# E-20_EXP_MicroSD_ADC.net
KiCad netlist of a schematic drawn in Altium Designer
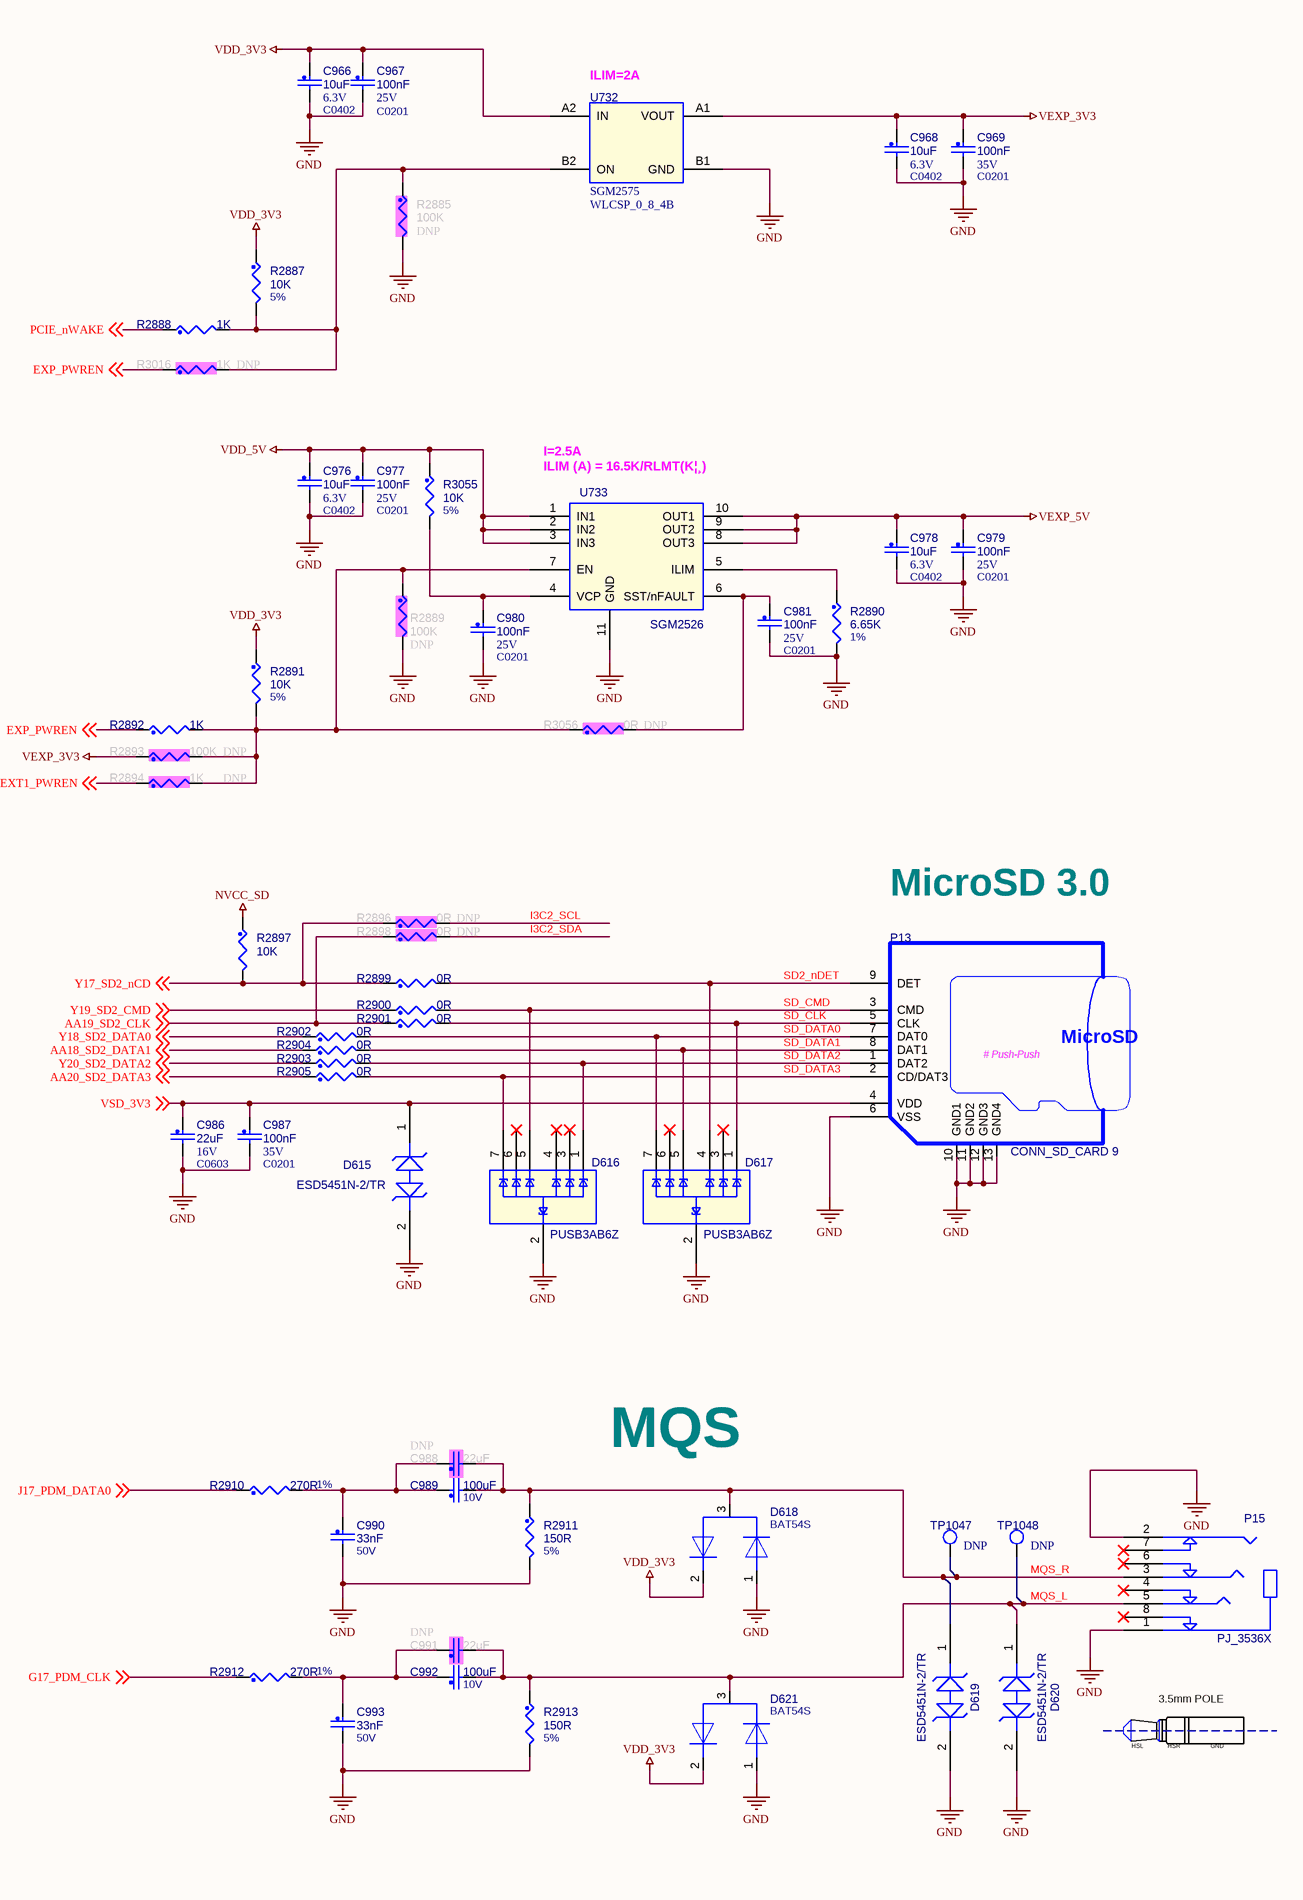
[diagram p0: E-20 EXP_MicroSD_ADC.SchDoc, left]
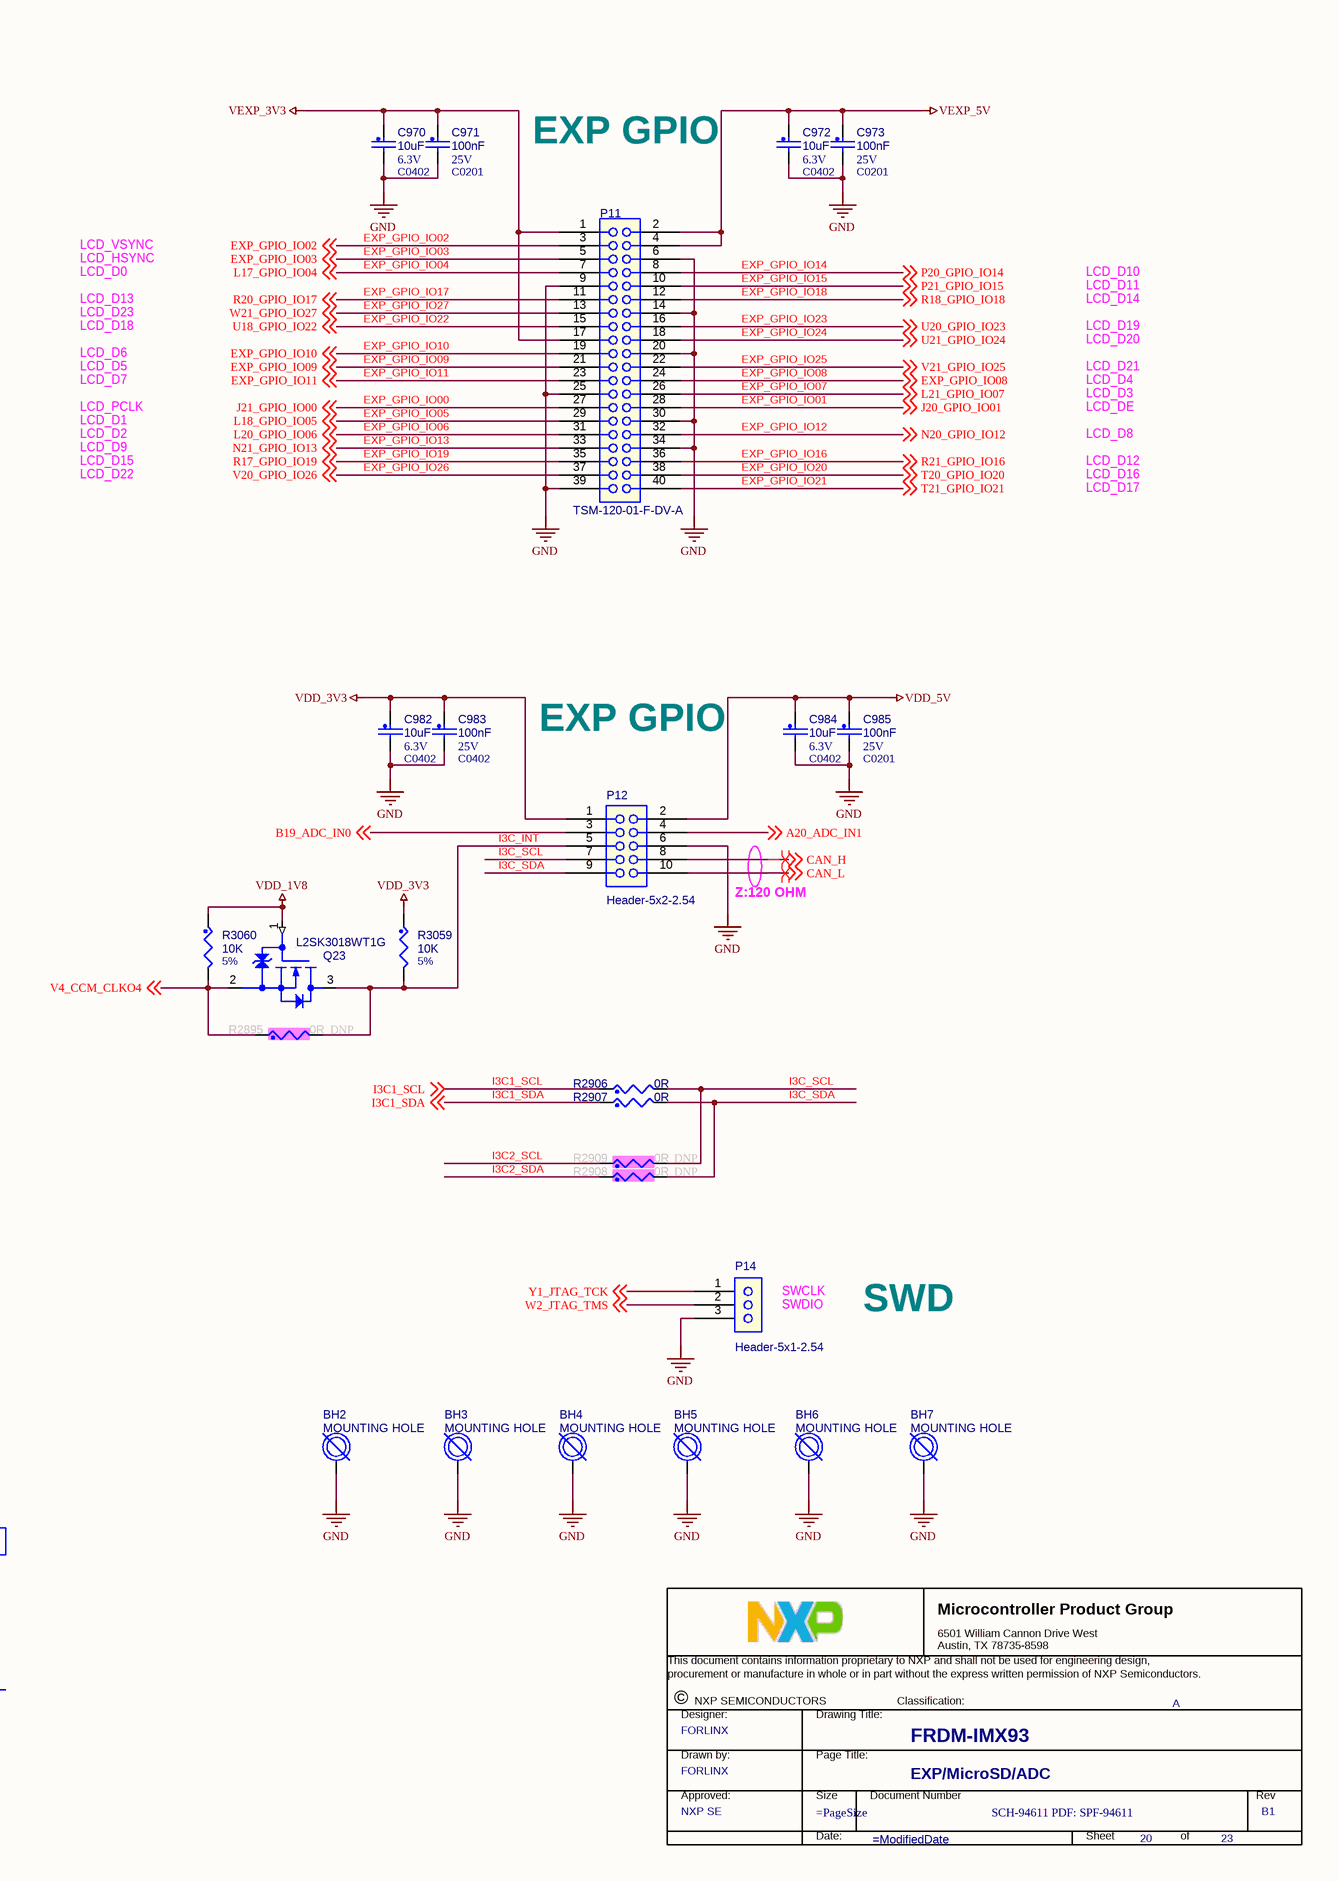
[diagram p1: E-20 EXP_MicroSD_ADC.SchDoc, right]

(export (version "E")
  (design (tool "Eeschema 10.0.6"))
  (components
    (comp (ref "BH2")
      (value "MOUNTING HOLE")
      (footprint "HOLE2_7_6")
      (description "no part to order")
      (libsource (lib "*") (part "MOUNT_HOLE"))
    )
    (comp (ref "BH3")
      (value "MOUNTING HOLE")
      (footprint "HOLE2_7_6")
      (description "no part to order")
      (libsource (lib "*") (part "MOUNT_HOLE"))
    )
    (comp (ref "BH4")
      (value "MOUNTING HOLE")
      (footprint "HOLE2_7_6")
      (description "no part to order")
      (libsource (lib "*") (part "MOUNT_HOLE"))
    )
    (comp (ref "BH5")
      (value "MOUNTING HOLE")
      (footprint "HOLE2_7_6")
      (description "no part to order")
      (libsource (lib "*") (part "MOUNT_HOLE"))
    )
    (comp (ref "BH6")
      (value "MOUNTING HOLE")
      (footprint "HOLE2_7_6")
      (description "no part to order")
      (libsource (lib "*") (part "MOUNT_HOLE"))
    )
    (comp (ref "BH7")
      (value "MOUNTING HOLE")
      (footprint "HOLE2_7_6")
      (description "no part to order")
      (libsource (lib "*") (part "MOUNT_HOLE"))
    )
    (comp (ref "C966")
      (value "10uF")
      (footprint "C0402")
      (description "0402,10uF,6.3V,+/-20%,X5R")
      (fields
        (field (name "TOLERANCE") "20%")
        (field (name "VOLTAGE") "6.3V")
        (field (name "PCB FOOTPRINT") "C0402")
      )
      (libsource (lib "*") (part "CAP_NP"))
    )
    (comp (ref "C967")
      (value "100nF")
      (footprint "C0201")
      (description "0201,100nF,25V,+/-10%,X5R")
      (fields
        (field (name "TOLERANCE") "10%")
        (field (name "VOLTAGE") "25V")
        (field (name "PCB FOOTPRINT") "C0201")
      )
      (libsource (lib "*") (part "CAP_NP"))
    )
    (comp (ref "C968")
      (value "10uF")
      (footprint "C0402")
      (description "0402,10uF,6.3V,+/-20%,X5R")
      (fields
        (field (name "VOLTAGE") "6.3V")
        (field (name "TOLERANCE") "20%")
        (field (name "PCB FOOTPRINT") "C0402")
      )
      (libsource (lib "*") (part "CAP_NP"))
    )
    (comp (ref "C969")
      (value "100nF")
      (footprint "C0201")
      (description "0201,100nF,25V,+/-10%,X5R")
      (fields
        (field (name "VOLTAGE") "35V")
        (field (name "TOLERANCE") "10%")
        (field (name "PCB FOOTPRINT") "C0201")
      )
      (libsource (lib "*") (part "CAP_NP"))
    )
    (comp (ref "C970")
      (value "10uF")
      (footprint "C0402")
      (description "0402,10uF,6.3V,+/-20%,X5R")
      (fields
        (field (name "VOLTAGE") "6.3V")
        (field (name "TOLERANCE") "20%")
        (field (name "PCB FOOTPRINT") "C0402")
      )
      (libsource (lib "*") (part "CAP_NP"))
    )
    (comp (ref "C971")
      (value "100nF")
      (footprint "C0201")
      (description "0201,100nF,25V,+/-10%,X5R")
      (fields
        (field (name "TOLERANCE") "10%")
        (field (name "VOLTAGE") "25V")
        (field (name "PCB FOOTPRINT") "C0201")
      )
      (libsource (lib "*") (part "CAP_NP"))
    )
    (comp (ref "C972")
      (value "10uF")
      (footprint "C0402")
      (description "0402,10uF,6.3V,+/-20%,X5R")
      (fields
        (field (name "VOLTAGE") "6.3V")
        (field (name "TOLERANCE") "20%")
        (field (name "PCB FOOTPRINT") "C0402")
      )
      (libsource (lib "*") (part "CAP_NP"))
    )
    (comp (ref "C973")
      (value "100nF")
      (footprint "C0201")
      (description "0201,100nF,25V,+/-10%,X5R")
      (fields
        (field (name "VOLTAGE") "25V")
        (field (name "TOLERANCE") "10%")
        (field (name "PCB FOOTPRINT") "C0201")
      )
      (libsource (lib "*") (part "CAP_NP"))
    )
    (comp (ref "C976")
      (value "10uF")
      (footprint "C0402")
      (description "0402,10uF,6.3V,+/-20%,X5R")
      (fields
        (field (name "VOLTAGE") "6.3V")
        (field (name "TOLERANCE") "20%")
        (field (name "PCB FOOTPRINT") "C0402")
      )
      (libsource (lib "*") (part "CAP_NP"))
    )
    (comp (ref "C977")
      (value "100nF")
      (footprint "C0201")
      (description "0201,100nF,25V,+/-10%,X5R")
      (fields
        (field (name "VOLTAGE") "25V")
        (field (name "TOLERANCE") "10%")
        (field (name "PCB FOOTPRINT") "C0201")
      )
      (libsource (lib "*") (part "CAP_NP"))
    )
    (comp (ref "C978")
      (value "10uF")
      (footprint "C0402")
      (description "0402,10uF,6.3V,+/-20%,X5R")
      (fields
        (field (name "TOLERANCE") "20%")
        (field (name "VOLTAGE") "6.3V")
        (field (name "PCB FOOTPRINT") "C0402")
      )
      (libsource (lib "*") (part "CAP_NP"))
    )
    (comp (ref "C979")
      (value "100nF")
      (footprint "C0201")
      (description "0201,100nF,25V,+/-10%,X5R")
      (fields
        (field (name "VOLTAGE") "25V")
        (field (name "TOLERANCE") "10%")
        (field (name "PCB FOOTPRINT") "C0201")
      )
      (libsource (lib "*") (part "CAP_NP"))
    )
    (comp (ref "C980")
      (value "100nF")
      (footprint "C0201")
      (description "0201,100nF,25V,+/-10%,X5R")
      (fields
        (field (name "TOLERANCE") "10%")
        (field (name "VOLTAGE") "25V")
        (field (name "PCB FOOTPRINT") "C0201")
      )
      (libsource (lib "*") (part "CAP_NP"))
    )
    (comp (ref "C981")
      (value "100nF")
      (footprint "C0201")
      (description "0201,100nF,25V,+/-10%,X5R")
      (fields
        (field (name "VOLTAGE") "25V")
        (field (name "TOLERANCE") "10%")
        (field (name "PCB FOOTPRINT") "C0201")
      )
      (libsource (lib "*") (part "CAP_NP"))
    )
    (comp (ref "C982")
      (value "10uF")
      (footprint "C0402")
      (description "0402,10uF,6.3V,+/-20%,X5R")
      (fields
        (field (name "TOLERANCE") "20%")
        (field (name "VOLTAGE") "6.3V")
        (field (name "PCB FOOTPRINT") "C0402")
      )
      (libsource (lib "*") (part "CAP_NP"))
    )
    (comp (ref "C983")
      (value "100nF")
      (footprint "C0402")
      (description "0402,100nF,50V,+/-10%,X5R")
      (fields
        (field (name "TOLERANCE") "10%")
        (field (name "VOLTAGE") "25V")
        (field (name "PCB FOOTPRINT") "C0402")
      )
      (libsource (lib "*") (part "CAP_NP"))
    )
    (comp (ref "C984")
      (value "10uF")
      (footprint "C0402")
      (description "0402,10uF,6.3V,+/-20%,X5R")
      (fields
        (field (name "VOLTAGE") "6.3V")
        (field (name "TOLERANCE") "20%")
        (field (name "PCB FOOTPRINT") "C0402")
      )
      (libsource (lib "*") (part "CAP_NP"))
    )
    (comp (ref "C985")
      (value "100nF")
      (footprint "C0201")
      (description "0201,100nF,25V,+/-10%,X5R")
      (fields
        (field (name "VOLTAGE") "25V")
        (field (name "TOLERANCE") "10%")
        (field (name "PCB FOOTPRINT") "C0201")
      )
      (libsource (lib "*") (part "CAP_NP"))
    )
    (comp (ref "C986")
      (value "22uF")
      (footprint "C0603")
      (description "0603,22uF,6.3V,+/-20%,X5R")
      (fields
        (field (name "VOLTAGE") "16V")
        (field (name "TOLERANCE") "20%")
        (field (name "PCB FOOTPRINT") "C0603")
      )
      (libsource (lib "*") (part "CAP_NP"))
    )
    (comp (ref "C987")
      (value "100nF")
      (footprint "C0201")
      (description "0201,100nF,25V,+/-10%,X5R")
      (fields
        (field (name "TOLERANCE") "10%")
        (field (name "VOLTAGE") "35V")
        (field (name "PCB FOOTPRINT") "C0201")
      )
      (libsource (lib "*") (part "CAP_NP"))
    )
    (comp (ref "C988")
      (value "22uF")
      (footprint "C0805")
      (description "0805,22uF,25V,+/-20%,X5R")
      (fields (field (name "ASSY_OPT") "DNP") (field (name "TOLERANCE") "20%"))
      (libsource (lib "*") (part "CAP_NP"))
    )
    (comp (ref "C989")
      (value "100uF")
      (footprint "C1206")
      (description "1206,100uF,6.3V,+/-20%,X5R")
      (fields (field (name "VOLTAGE") "10V") (field (name "TOLERANCE") "20%"))
      (libsource (lib "*") (part "CAP_NP"))
    )
    (comp (ref "C990")
      (value "33nF")
      (footprint "C0402")
      (description "0402,33nF,50V,+/-10%,X7R")
      (fields (field (name "VOLTAGE") "50V") (field (name "TOLERANCE") "10%"))
      (libsource (lib "*") (part "CAP_NP"))
    )
    (comp (ref "C991")
      (value "22uF")
      (footprint "C0805")
      (description "0805,22uF,25V,+/-20%,X5R")
      (fields (field (name "ASSY_OPT") "DNP") (field (name "TOLERANCE") "20%"))
      (libsource (lib "*") (part "CAP_NP"))
    )
    (comp (ref "C992")
      (value "100uF")
      (footprint "C1206")
      (description "1206,100uF,6.3V,+/-20%,X5R")
      (fields (field (name "VOLTAGE") "10V") (field (name "TOLERANCE") "20%"))
      (libsource (lib "*") (part "CAP_NP"))
    )
    (comp (ref "C993")
      (value "33nF")
      (footprint "C0402")
      (description "0402,33nF,50V,+/-10%,X7R")
      (fields (field (name "TOLERANCE") "10%") (field (name "VOLTAGE") "50V"))
      (libsource (lib "*") (part "CAP_NP"))
    )
    (comp (ref "D615")
      (value "ESD5451N-2/TR")
      (footprint "0402TVS")
      (libsource (lib "*") (part "ESD5451N-2/TR"))
    )
    (comp (ref "D616") (value "PUSB3AB6Z") (footprint "DFN2111_7") (libsource (lib "*") (part "PUSB3AB6Z")))
    (comp (ref "D617") (value "PUSB3AB6Z") (footprint "DFN2111_7") (libsource (lib "*") (part "PUSB3AB6Z")))
    (comp (ref "D618")
      (value "BAT54S")
      (footprint "sot23_a")
      (description "BAT54S,SOT-23-3")
      (libsource (lib "*") (part "BAV99W"))
    )
    (comp (ref "D619")
      (value "ESD5451N-2/TR")
      (footprint "0402TVS")
      (libsource (lib "*") (part "ESD5451N-2/TR"))
    )
    (comp (ref "D620")
      (value "ESD5451N-2/TR")
      (footprint "0402TVS")
      (libsource (lib "*") (part "ESD5451N-2/TR"))
    )
    (comp (ref "D621")
      (value "BAT54S")
      (footprint "sot23_a")
      (description "BAT54S,SOT-23-3")
      (libsource (lib "*") (part "BAV99W"))
    )
    (comp (ref "P11")
      (value "TSM-120-01-F-DV-A")
      (footprint "hdr220_tsm_a_sm")
      (description "Double row, 2 * 20P, 2.54mm, S, gold-plated, green")
      (libsource (lib "*") (part "CONN_HDR_19"))
    )
    (comp (ref "P12")
      (value "Header-5x2-2.54")
      (footprint "Header5x2_25")
      (description "Double row,2*5P,2.54mm,S")
      (libsource (lib "*") (part "Header-5x2-2_0.54"))
    )
    (comp (ref "P13")
      (value "CONN_SD_CARD 9")
      (footprint "con9_sdcard_1p1mm")
      (description "TFP09-2-12B")
      (libsource (lib "*") (part "CONN_MICRO_SDCARD"))
    )
    (comp (ref "P14")
      (value "Header-5x1-2.54")
      (footprint "Header_2_54_3p")
      (description "Single row,3P,2.54mm,S")
      (libsource (lib "*") (part "Header-5x1-2_0.54"))
    )
    (comp (ref "P15")
      (value "PJ_3536X")
      (footprint "PJ3930_8P")
      (description "PJ3930-8P,3.5mm,Level 4")
      (libsource (lib "*") (part "PJ_3536X"))
    )
    (comp (ref "Q23")
      (value "L2SK3018WT1G")
      (footprint "sc70_3")
      (libsource (lib "*") (part "NX3008NBKW_SOT323"))
    )
    (comp (ref "R2885")
      (value "100K")
      (footprint "R0201")
      (description "0201,100K,+/-1%")
      (fields (field (name "ASSY_OPT") "DNP") (field (name "TOLERANCE") "1%"))
      (libsource (lib "*") (part "RES"))
    )
    (comp (ref "R2887")
      (value "10K")
      (footprint "R0201")
      (description "0201,10K,+/-5%")
      (fields (field (name "TOLERANCE") "5%"))
      (libsource (lib "*") (part "RES"))
    )
    (comp (ref "R2888")
      (value "1K")
      (footprint "R0201")
      (description "0201,1K,+/-1%")
      (fields (field (name "VOLTAGE") "1/16W") (field (name "TOLERANCE") "5%"))
      (libsource (lib "*") (part "RES"))
    )
    (comp (ref "R2889")
      (value "100K")
      (footprint "R0201")
      (description "0201,100K,+/-1%")
      (fields (field (name "ASSY_OPT") "DNP") (field (name "TOLERANCE") "1%"))
      (libsource (lib "*") (part "RES"))
    )
    (comp (ref "R2890")
      (value "6.65K")
      (footprint "R0402")
      (description "0402,6.65K,+/-1%")
      (fields (field (name "TOLERANCE") "1%"))
      (libsource (lib "*") (part "RES"))
    )
    (comp (ref "R2891")
      (value "10K")
      (footprint "R0201")
      (description "0201,10K,+/-5%")
      (fields (field (name "TOLERANCE") "5%"))
      (libsource (lib "*") (part "RES"))
    )
    (comp (ref "R2892")
      (value "1K")
      (footprint "R0201")
      (description "0201,1K,+/-1%")
      (fields (field (name "VOLTAGE") "1/16W") (field (name "TOLERANCE") "5%"))
      (libsource (lib "*") (part "RES"))
    )
    (comp (ref "R2893")
      (value "100K")
      (footprint "R0201")
      (description "0201,100K,+/-1%")
      (fields
        (field (name "ASSY_OPT") "DNP")
        (field (name "VOLTAGE") "1/16W")
        (field (name "TOLERANCE") "5%")
      )
      (libsource (lib "*") (part "RES"))
    )
    (comp (ref "R2894")
      (value "1K")
      (footprint "R0201")
      (description "0201,1K,+/-1%")
      (fields
        (field (name "ASSY_OPT") "DNP")
        (field (name "VOLTAGE") "1/16W")
        (field (name "TOLERANCE") "5%")
      )
      (libsource (lib "*") (part "RES"))
    )
    (comp (ref "R2895")
      (value "0R")
      (footprint "R0201")
      (description "0201,0Ohm,+/-5%")
      (fields
        (field (name "ASSY_OPT") "DNP")
        (field (name "VOLTAGE") "1/16W")
        (field (name "TOLERANCE") "5%")
      )
      (libsource (lib "*") (part "RES"))
    )
    (comp (ref "R2896")
      (value "0R")
      (footprint "R0201")
      (description "0201,0Ohm,+/-5%")
      (fields
        (field (name "ASSY_OPT") "DNP")
        (field (name "TOLERANCE") "5%")
        (field (name "VOLTAGE") "1/16W")
      )
      (libsource (lib "*") (part "RES"))
    )
    (comp (ref "R2897")
      (value "10K")
      (footprint "R0201")
      (description "0201,10K,+/-5%")
      (fields (field (name "TOLERANCE") "5%"))
      (libsource (lib "*") (part "RES"))
    )
    (comp (ref "R2898")
      (value "0R")
      (footprint "R0201")
      (description "0201,0Ohm,+/-5%")
      (fields
        (field (name "ASSY_OPT") "DNP")
        (field (name "TOLERANCE") "5%")
        (field (name "VOLTAGE") "1/16W")
      )
      (libsource (lib "*") (part "RES"))
    )
    (comp (ref "R2899")
      (value "0R")
      (footprint "R0201")
      (description "0201,0Ohm,+/-5%")
      (fields (field (name "TOLERANCE") "5%") (field (name "VOLTAGE") "1/16W"))
      (libsource (lib "*") (part "RES"))
    )
    (comp (ref "R2900")
      (value "0R")
      (footprint "R0201")
      (description "0201,0Ohm,+/-5%")
      (fields (field (name "VOLTAGE") "1/16W") (field (name "TOLERANCE") "5%"))
      (libsource (lib "*") (part "RES"))
    )
    (comp (ref "R2901")
      (value "0R")
      (footprint "R0201")
      (description "0201,0Ohm,+/-5%")
      (fields (field (name "VOLTAGE") "1/16W") (field (name "TOLERANCE") "5%"))
      (libsource (lib "*") (part "RES"))
    )
    (comp (ref "R2902")
      (value "0R")
      (footprint "R0201")
      (description "0201,0Ohm,+/-5%")
      (fields (field (name "VOLTAGE") "1/16W") (field (name "TOLERANCE") "5%"))
      (libsource (lib "*") (part "RES"))
    )
    (comp (ref "R2903")
      (value "0R")
      (footprint "R0201")
      (description "0201,0Ohm,+/-5%")
      (fields (field (name "TOLERANCE") "5%") (field (name "VOLTAGE") "1/16W"))
      (libsource (lib "*") (part "RES"))
    )
    (comp (ref "R2904")
      (value "0R")
      (footprint "R0201")
      (description "0201,0Ohm,+/-5%")
      (fields (field (name "TOLERANCE") "5%") (field (name "VOLTAGE") "1/16W"))
      (libsource (lib "*") (part "RES"))
    )
    (comp (ref "R2905")
      (value "0R")
      (footprint "R0201")
      (description "0201,0Ohm,+/-5%")
      (fields (field (name "VOLTAGE") "1/16W") (field (name "TOLERANCE") "5%"))
      (libsource (lib "*") (part "RES"))
    )
    (comp (ref "R2906")
      (value "0R")
      (footprint "R0201")
      (description "0201,0Ohm,+/-5%")
      (fields (field (name "VOLTAGE") "1/16W") (field (name "TOLERANCE") "5%"))
      (libsource (lib "*") (part "RES"))
    )
    (comp (ref "R2907")
      (value "0R")
      (footprint "R0201")
      (description "0201,0Ohm,+/-5%")
      (fields (field (name "VOLTAGE") "1/16W") (field (name "TOLERANCE") "5%"))
      (libsource (lib "*") (part "RES"))
    )
    (comp (ref "R2908")
      (value "0R")
      (footprint "R0201")
      (description "0201,0Ohm,+/-5%")
      (fields
        (field (name "ASSY_OPT") "DNP")
        (field (name "TOLERANCE") "5%")
        (field (name "VOLTAGE") "1/16W")
      )
      (libsource (lib "*") (part "RES"))
    )
    (comp (ref "R2909")
      (value "0R")
      (footprint "R0201")
      (description "0201,0Ohm,+/-5%")
      (fields
        (field (name "ASSY_OPT") "DNP")
        (field (name "TOLERANCE") "5%")
        (field (name "VOLTAGE") "1/16W")
      )
      (libsource (lib "*") (part "RES"))
    )
    (comp (ref "R2910")
      (value "270R")
      (footprint "R0402")
      (description "0402,270Ohm,+/-5%")
      (fields (field (name "VOLTAGE") "50V") (field (name "TOLERANCE") "1%"))
      (libsource (lib "*") (part "RES"))
    )
    (comp (ref "R2911")
      (value "150R")
      (footprint "R0402")
      (description "0402,150Ohm,+/-5%")
      (fields (field (name "VOLTAGE") "1/16W") (field (name "TOLERANCE") "5%"))
      (libsource (lib "*") (part "RES"))
    )
    (comp (ref "R2912")
      (value "270R")
      (footprint "R0402")
      (description "0402,270Ohm,+/-5%")
      (fields (field (name "TOLERANCE") "1%") (field (name "VOLTAGE") "50V"))
      (libsource (lib "*") (part "RES"))
    )
    (comp (ref "R2913")
      (value "150R")
      (footprint "R0402")
      (description "0402,150Ohm,+/-5%")
      (fields (field (name "TOLERANCE") "5%") (field (name "VOLTAGE") "1/16W"))
      (libsource (lib "*") (part "RES"))
    )
    (comp (ref "R3016")
      (value "1K")
      (footprint "R0201")
      (description "0201,1K,+/-1%")
      (fields
        (field (name "ASSY_OPT") "DNP")
        (field (name "VOLTAGE") "1/16W")
        (field (name "TOLERANCE") "5%")
      )
      (libsource (lib "*") (part "RES"))
    )
    (comp (ref "R3055")
      (value "10K")
      (footprint "R0201")
      (description "0201,10K,+/-5%")
      (fields (field (name "TOLERANCE") "5%"))
      (libsource (lib "*") (part "RES"))
    )
    (comp (ref "R3056")
      (value "0R")
      (footprint "R0201")
      (description "0201,0Ohm,+/-5%")
      (fields
        (field (name "ASSY_OPT") "DNP")
        (field (name "VOLTAGE") "1/16W")
        (field (name "TOLERANCE") "5%")
      )
      (libsource (lib "*") (part "RES"))
    )
    (comp (ref "R3059")
      (value "10K")
      (footprint "R0201")
      (description "0201,10K,+/-5%")
      (fields (field (name "TOLERANCE") "5%"))
      (libsource (lib "*") (part "RES"))
    )
    (comp (ref "R3060")
      (value "10K")
      (footprint "R0201")
      (description "0201,10K,+/-5%")
      (fields (field (name "TOLERANCE") "5%"))
      (libsource (lib "*") (part "RES"))
    )
    (comp (ref "TP1047")
      (value "TPAD_020")
      (footprint "tpad_020")
      (description "no part to order")
      (fields (field (name "ASSY_OPT") "DNP"))
      (libsource (lib "*") (part "T POINT R"))
    )
    (comp (ref "TP1048")
      (value "TPAD_020")
      (footprint "tpad_020")
      (description "no part to order")
      (fields (field (name "ASSY_OPT") "DNP"))
      (libsource (lib "*") (part "T POINT R"))
    )
    (comp (ref "U732")
      (value "SGM2575")
      (footprint "WLCSP_0_8_4B")
      (description "SGM2575AD,WLCSP_4B,0.8*0.8mm,-40~85+C")
      (fields (field (name "PCB FOOTPRINT") "WLCSP_0_8_4B"))
      (libsource (lib "*") (part "CW3301_Load Switch"))
    )
    (comp (ref "U733")
      (value "SGM2526")
      (footprint "tdfn_3x3_10l")
      (description "SGM2526YTD10G/TR,TDFN-3x3-10L,-40+C~85+C,Imax 5A")
      (libsource (lib "*") (part "SGM2526_2"))
    )
  )
  (nets
    (net (code "1") (name "/I3C2_SCL") (class "Default")
      (node (ref "R2896") (pin "2") (pinfunction "2_2") (pintype "passive"))
      (node (ref "R2909") (pin "1") (pinfunction "1_1") (pintype "passive"))
    )
    (net (code "2") (name "/I3C2_SDA") (class "Default")
      (node (ref "R2898") (pin "2") (pinfunction "2_2") (pintype "passive"))
      (node (ref "R2908") (pin "1") (pinfunction "1_1") (pintype "passive"))
    )
    (net (code "3") (name "/I3C_INT") (class "Default")
      (node (ref "P12") (pin "5") (pinfunction "A3_5") (pintype "passive"))
      (node (ref "Q23") (pin "3") (pinfunction "DRAIN_3") (pintype "passive"))
      (node (ref "R2895") (pin "2") (pinfunction "2_2") (pintype "passive"))
      (node (ref "R3059") (pin "2") (pinfunction "2_2") (pintype "passive"))
    )
    (net (code "4") (name "/I3C_SCL") (class "Default")
      (node (ref "P12") (pin "7") (pinfunction "A4_7") (pintype "passive"))
      (node (ref "R2906") (pin "2") (pinfunction "2_2") (pintype "passive"))
      (node (ref "R2909") (pin "2") (pinfunction "2_2") (pintype "passive"))
    )
    (net (code "5") (name "/I3C_SDA") (class "Default")
      (node (ref "P12") (pin "9") (pinfunction "A5_9") (pintype "passive"))
      (node (ref "R2907") (pin "2") (pinfunction "2_2") (pintype "passive"))
      (node (ref "R2908") (pin "2") (pinfunction "2_2") (pintype "passive"))
    )
    (net (code "6") (name "/MQS_L") (class "Default")
      (node (ref "C991") (pin "2") (pinfunction "2_2") (pintype "passive"))
      (node (ref "C992") (pin "2") (pinfunction "2_2") (pintype "passive"))
      (node (ref "D620") (pin "1") (pinfunction "1_1") (pintype "passive"))
      (node (ref "D621") (pin "3") (pinfunction "CATHODE/ANODE_3") (pintype "passive"))
      (node (ref "P15") (pin "5") (pinfunction "5_5") (pintype "passive"))
      (node (ref "R2913") (pin "1") (pinfunction "1_1") (pintype "passive"))
      (node (ref "TP1048") (pin "1") (pinfunction "TP_1") (pintype "passive"))
    )
    (net (code "7") (name "/MQS_R") (class "Default")
      (node (ref "C988") (pin "2") (pinfunction "2_2") (pintype "passive"))
      (node (ref "C989") (pin "2") (pinfunction "2_2") (pintype "passive"))
      (node (ref "D618") (pin "3") (pinfunction "CATHODE/ANODE_3") (pintype "passive"))
      (node (ref "D619") (pin "1") (pinfunction "1_1") (pintype "passive"))
      (node (ref "P15") (pin "3") (pinfunction "3_3") (pintype "passive"))
      (node (ref "R2911") (pin "1") (pinfunction "1_1") (pintype "passive"))
      (node (ref "TP1047") (pin "1") (pinfunction "TP_1") (pintype "passive"))
    )
    (net (code "8") (name "/SD2_nDET") (class "Default")
      (node (ref "D617") (pin "4") (pinfunction "4_4") (pintype "passive"))
      (node (ref "P13") (pin "9") (pinfunction "DET_9") (pintype "passive"))
      (node (ref "R2899") (pin "2") (pinfunction "2_2") (pintype "passive"))
    )
    (net (code "9") (name "/SD_CLK") (class "Default")
      (node (ref "D617") (pin "1") (pinfunction "1_1") (pintype "passive"))
      (node (ref "P13") (pin "5") (pinfunction "CLK_5") (pintype "passive"))
      (node (ref "R2901") (pin "2") (pinfunction "2_2") (pintype "passive"))
    )
    (net (code "10") (name "/SD_CMD") (class "Default")
      (node (ref "D616") (pin "5") (pinfunction "5_5") (pintype "passive"))
      (node (ref "P13") (pin "3") (pinfunction "CMD_3") (pintype "passive"))
      (node (ref "R2900") (pin "2") (pinfunction "2_2") (pintype "passive"))
    )
    (net (code "11") (name "/SD_DATA0") (class "Default")
      (node (ref "D617") (pin "7") (pinfunction "7_7") (pintype "passive"))
      (node (ref "P13") (pin "7") (pinfunction "DAT0_7") (pintype "passive"))
      (node (ref "R2902") (pin "2") (pinfunction "2_2") (pintype "passive"))
    )
    (net (code "12") (name "/SD_DATA1") (class "Default")
      (node (ref "D617") (pin "5") (pinfunction "5_5") (pintype "passive"))
      (node (ref "P13") (pin "8") (pinfunction "DAT1_8") (pintype "passive"))
      (node (ref "R2904") (pin "2") (pinfunction "2_2") (pintype "passive"))
    )
    (net (code "13") (name "/SD_DATA2") (class "Default")
      (node (ref "D616") (pin "1") (pinfunction "1_1") (pintype "passive"))
      (node (ref "P13") (pin "1") (pinfunction "DAT2_1") (pintype "passive"))
      (node (ref "R2903") (pin "2") (pinfunction "2_2") (pintype "passive"))
    )
    (net (code "14") (name "/SD_DATA3") (class "Default")
      (node (ref "D616") (pin "7") (pinfunction "7_7") (pintype "passive"))
      (node (ref "P13") (pin "2") (pinfunction "CD/DAT3_2") (pintype "passive"))
      (node (ref "R2905") (pin "2") (pinfunction "2_2") (pintype "passive"))
    )
    (net (code "15") (name "A20_ADC_IN1") (class "Default")
      (node (ref "P12") (pin "4") (pinfunction "B2_4") (pintype "passive"))
    )
    (net (code "16") (name "AA18_SD2_DATA1") (class "Default")
      (node (ref "R2904") (pin "1") (pinfunction "1_1") (pintype "passive"))
    )
    (net (code "17") (name "AA19_SD2_CLK") (class "Default")
      (node (ref "R2898") (pin "1") (pinfunction "1_1") (pintype "passive"))
      (node (ref "R2901") (pin "1") (pinfunction "1_1") (pintype "passive"))
    )
    (net (code "18") (name "AA20_SD2_DATA3") (class "Default")
      (node (ref "R2905") (pin "1") (pinfunction "1_1") (pintype "passive"))
    )
    (net (code "19") (name "B19_ADC_IN0") (class "Default")
      (node (ref "P12") (pin "3") (pinfunction "A2_3") (pintype "passive"))
    )
    (net (code "20") (name "CAN_H") (class "Default")
      (node (ref "P12") (pin "8") (pinfunction "B4_8") (pintype "passive"))
    )
    (net (code "21") (name "CAN_L") (class "Default")
      (node (ref "P12") (pin "10") (pinfunction "B5_10") (pintype "passive"))
    )
    (net (code "22") (name "EXP_GPIO_IO02") (class "Default")
      (node (ref "P11") (pin "3") (pinfunction "A2_3") (pintype "passive"))
    )
    (net (code "23") (name "EXP_GPIO_IO03") (class "Default")
      (node (ref "P11") (pin "5") (pinfunction "A3_5") (pintype "passive"))
    )
    (net (code "24") (name "EXP_GPIO_IO08") (class "Default")
      (node (ref "P11") (pin "24") (pinfunction "B12_24") (pintype "passive"))
    )
    (net (code "25") (name "EXP_GPIO_IO09") (class "Default")
      (node (ref "P11") (pin "21") (pinfunction "A11_21") (pintype "passive"))
    )
    (net (code "26") (name "EXP_GPIO_IO10") (class "Default")
      (node (ref "P11") (pin "19") (pinfunction "A10_19") (pintype "passive"))
    )
    (net (code "27") (name "EXP_GPIO_IO11") (class "Default")
      (node (ref "P11") (pin "23") (pinfunction "A12_23") (pintype "passive"))
    )
    (net (code "28") (name "EXP_PWREN") (class "Default")
      (node (ref "R2892") (pin "1") (pinfunction "1_1") (pintype "passive"))
      (node (ref "R3016") (pin "1") (pinfunction "1_1") (pintype "passive"))
    )
    (net (code "29") (name "EXT1_PWREN") (class "Default")
      (node (ref "R2894") (pin "1") (pinfunction "1_1") (pintype "passive"))
    )
    (net (code "30") (name "G17_PDM_CLK") (class "Default")
      (node (ref "R2912") (pin "1") (pinfunction "1_1") (pintype "passive"))
    )
    (net (code "31") (name "GND") (class "Default")
      (node (ref "BH2") (pin "1") (pinfunction "1_1") (pintype "passive"))
      (node (ref "BH3") (pin "1") (pinfunction "1_1") (pintype "passive"))
      (node (ref "BH4") (pin "1") (pinfunction "1_1") (pintype "passive"))
      (node (ref "BH5") (pin "1") (pinfunction "1_1") (pintype "passive"))
      (node (ref "BH6") (pin "1") (pinfunction "1_1") (pintype "passive"))
      (node (ref "BH7") (pin "1") (pinfunction "1_1") (pintype "passive"))
      (node (ref "C966") (pin "2") (pinfunction "2_2") (pintype "passive"))
      (node (ref "C967") (pin "2") (pinfunction "2_2") (pintype "passive"))
      (node (ref "C968") (pin "2") (pinfunction "2_2") (pintype "passive"))
      (node (ref "C969") (pin "2") (pinfunction "2_2") (pintype "passive"))
      (node (ref "C970") (pin "2") (pinfunction "2_2") (pintype "passive"))
      (node (ref "C971") (pin "2") (pinfunction "2_2") (pintype "passive"))
      (node (ref "C972") (pin "2") (pinfunction "2_2") (pintype "passive"))
      (node (ref "C973") (pin "2") (pinfunction "2_2") (pintype "passive"))
      (node (ref "C976") (pin "2") (pinfunction "2_2") (pintype "passive"))
      (node (ref "C977") (pin "2") (pinfunction "2_2") (pintype "passive"))
      (node (ref "C978") (pin "2") (pinfunction "2_2") (pintype "passive"))
      (node (ref "C979") (pin "2") (pinfunction "2_2") (pintype "passive"))
      (node (ref "C980") (pin "2") (pinfunction "2_2") (pintype "passive"))
      (node (ref "C981") (pin "2") (pinfunction "2_2") (pintype "passive"))
      (node (ref "C982") (pin "2") (pinfunction "2_2") (pintype "passive"))
      (node (ref "C983") (pin "2") (pinfunction "2_2") (pintype "passive"))
      (node (ref "C984") (pin "2") (pinfunction "2_2") (pintype "passive"))
      (node (ref "C985") (pin "2") (pinfunction "2_2") (pintype "passive"))
      (node (ref "C986") (pin "2") (pinfunction "2_2") (pintype "passive"))
      (node (ref "C987") (pin "2") (pinfunction "2_2") (pintype "passive"))
      (node (ref "C990") (pin "2") (pinfunction "2_2") (pintype "passive"))
      (node (ref "C993") (pin "2") (pinfunction "2_2") (pintype "passive"))
      (node (ref "D615") (pin "2") (pinfunction "2_2") (pintype "passive"))
      (node (ref "D616") (pin "2") (pinfunction "2_2") (pintype "passive"))
      (node (ref "D617") (pin "2") (pinfunction "2_2") (pintype "passive"))
      (node (ref "D618") (pin "1") (pinfunction "ANODE_1") (pintype "passive"))
      (node (ref "D619") (pin "2") (pinfunction "2_2") (pintype "passive"))
      (node (ref "D620") (pin "2") (pinfunction "2_2") (pintype "passive"))
      (node (ref "D621") (pin "1") (pinfunction "ANODE_1") (pintype "passive"))
      (node (ref "P11") (pin "14") (pinfunction "B7_14") (pintype "passive"))
      (node (ref "P11") (pin "20") (pinfunction "B10_20") (pintype "passive"))
      (node (ref "P11") (pin "25") (pinfunction "A13_25") (pintype "passive"))
      (node (ref "P11") (pin "30") (pinfunction "B15_30") (pintype "passive"))
      (node (ref "P11") (pin "34") (pinfunction "B17_34") (pintype "passive"))
      (node (ref "P11") (pin "39") (pinfunction "A20_39") (pintype "passive"))
      (node (ref "P11") (pin "6") (pinfunction "B3_6") (pintype "passive"))
      (node (ref "P11") (pin "9") (pinfunction "A5_9") (pintype "passive"))
      (node (ref "P12") (pin "6") (pinfunction "B3_6") (pintype "passive"))
      (node (ref "P13") (pin "10") (pinfunction "GND1_10") (pintype "power_in"))
      (node (ref "P13") (pin "11") (pinfunction "GND2_11") (pintype "power_in"))
      (node (ref "P13") (pin "12") (pinfunction "GND3_12") (pintype "power_in"))
      (node (ref "P13") (pin "13") (pinfunction "GND4_13") (pintype "power_in"))
      (node (ref "P13") (pin "6") (pinfunction "VSS_6") (pintype "power_in"))
      (node (ref "P14") (pin "3") (pinfunction "3_3") (pintype "passive"))
      (node (ref "P15") (pin "1") (pinfunction "1_1") (pintype "passive"))
      (node (ref "P15") (pin "2") (pinfunction "2_2") (pintype "passive"))
      (node (ref "R2885") (pin "2") (pinfunction "2_2") (pintype "passive"))
      (node (ref "R2889") (pin "2") (pinfunction "2_2") (pintype "passive"))
      (node (ref "R2890") (pin "2") (pinfunction "2_2") (pintype "passive"))
      (node (ref "R2911") (pin "2") (pinfunction "2_2") (pintype "passive"))
      (node (ref "R2913") (pin "2") (pinfunction "2_2") (pintype "passive"))
      (node (ref "U732") (pin "B1") (pinfunction "GND_B1") (pintype "passive"))
      (node (ref "U733") (pin "11") (pinfunction "GND_11") (pintype "passive"))
    )
    (net (code "32") (name "I3C1_SCL") (class "Default")
      (node (ref "R2906") (pin "1") (pinfunction "1_1") (pintype "passive"))
    )
    (net (code "33") (name "I3C1_SDA") (class "Default")
      (node (ref "R2907") (pin "1") (pinfunction "1_1") (pintype "passive"))
    )
    (net (code "34") (name "J17_PDM_DATA0") (class "Default")
      (node (ref "R2910") (pin "1") (pinfunction "1_1") (pintype "passive"))
    )
    (net (code "35") (name "J20_GPIO_IO01") (class "Default")
      (node (ref "P11") (pin "28") (pinfunction "B14_28") (pintype "passive"))
    )
    (net (code "36") (name "J21_GPIO_IO00") (class "Default")
      (node (ref "P11") (pin "27") (pinfunction "A14_27") (pintype "passive"))
    )
    (net (code "37") (name "L17_GPIO_IO04") (class "Default")
      (node (ref "P11") (pin "7") (pinfunction "A4_7") (pintype "passive"))
    )
    (net (code "38") (name "L18_GPIO_IO05") (class "Default")
      (node (ref "P11") (pin "29") (pinfunction "A15_29") (pintype "passive"))
    )
    (net (code "39") (name "L20_GPIO_IO06") (class "Default")
      (node (ref "P11") (pin "31") (pinfunction "A16_31") (pintype "passive"))
    )
    (net (code "40") (name "L21_GPIO_IO07") (class "Default")
      (node (ref "P11") (pin "26") (pinfunction "B13_26") (pintype "passive"))
    )
    (net (code "41") (name "N20_GPIO_IO12") (class "Default")
      (node (ref "P11") (pin "32") (pinfunction "B16_32") (pintype "passive"))
    )
    (net (code "42") (name "N21_GPIO_IO13") (class "Default")
      (node (ref "P11") (pin "33") (pinfunction "A17_33") (pintype "passive"))
    )
    (net (code "43") (name "NVCC_SD") (class "Default")
      (node (ref "R2897") (pin "1") (pinfunction "1_1") (pintype "passive"))
    )
    (net (code "44") (name "Net-(C988-Pad1)") (class "Default")
      (node (ref "C988") (pin "1") (pinfunction "1_1") (pintype "passive"))
      (node (ref "C989") (pin "1") (pinfunction "1_1") (pintype "passive"))
      (node (ref "C990") (pin "1") (pinfunction "1_1") (pintype "passive"))
      (node (ref "R2910") (pin "2") (pinfunction "2_2") (pintype "passive"))
    )
    (net (code "45") (name "Net-(C991-Pad1)") (class "Default")
      (node (ref "C991") (pin "1") (pinfunction "1_1") (pintype "passive"))
      (node (ref "C992") (pin "1") (pinfunction "1_1") (pintype "passive"))
      (node (ref "C993") (pin "1") (pinfunction "1_1") (pintype "passive"))
      (node (ref "R2912") (pin "2") (pinfunction "2_2") (pintype "passive"))
    )
    (net (code "46") (name "Net-(U732-ON)") (class "Default")
      (node (ref "R2885") (pin "1") (pinfunction "1_1") (pintype "passive"))
      (node (ref "R2887") (pin "2") (pinfunction "2_2") (pintype "passive"))
      (node (ref "R2888") (pin "2") (pinfunction "2_2") (pintype "passive"))
      (node (ref "R3016") (pin "2") (pinfunction "2_2") (pintype "passive"))
      (node (ref "U732") (pin "B2") (pinfunction "ON_B2") (pintype "passive"))
    )
    (net (code "47") (name "Net-(U733-EN)") (class "Default")
      (node (ref "R2889") (pin "1") (pinfunction "1_1") (pintype "passive"))
      (node (ref "R2891") (pin "2") (pinfunction "2_2") (pintype "passive"))
      (node (ref "R2892") (pin "2") (pinfunction "2_2") (pintype "passive"))
      (node (ref "R2893") (pin "2") (pinfunction "2_2") (pintype "passive"))
      (node (ref "R2894") (pin "2") (pinfunction "2_2") (pintype "passive"))
      (node (ref "R3056") (pin "1") (pinfunction "1_1") (pintype "passive"))
      (node (ref "U733") (pin "7") (pinfunction "EN_7") (pintype "passive"))
    )
    (net (code "48") (name "Net-(U733-ILIM)") (class "Default")
      (node (ref "R2890") (pin "1") (pinfunction "1_1") (pintype "passive"))
      (node (ref "U733") (pin "5") (pinfunction "ILIM_5") (pintype "passive"))
    )
    (net (code "49") (name "Net-(U733-SST{slash}nFAULT)") (class "Default")
      (node (ref "C981") (pin "1") (pinfunction "1_1") (pintype "passive"))
      (node (ref "R3056") (pin "2") (pinfunction "2_2") (pintype "passive"))
      (node (ref "U733") (pin "6") (pinfunction "SST/nFAULT_6") (pintype "passive"))
    )
    (net (code "50") (name "Net-(U733-VCP)") (class "Default")
      (node (ref "C980") (pin "1") (pinfunction "1_1") (pintype "passive"))
      (node (ref "R3055") (pin "2") (pinfunction "2_2") (pintype "passive"))
      (node (ref "U733") (pin "4") (pinfunction "VCP_4") (pintype "passive"))
    )
    (net (code "51") (name "P20_GPIO_IO14") (class "Default")
      (node (ref "P11") (pin "8") (pinfunction "B4_8") (pintype "passive"))
    )
    (net (code "52") (name "P21_GPIO_IO15") (class "Default")
      (node (ref "P11") (pin "10") (pinfunction "B5_10") (pintype "passive"))
    )
    (net (code "53") (name "PCIE_nWAKE") (class "Default")
      (node (ref "R2888") (pin "1") (pinfunction "1_1") (pintype "passive"))
    )
    (net (code "54") (name "R17_GPIO_IO19") (class "Default")
      (node (ref "P11") (pin "35") (pinfunction "A18_35") (pintype "passive"))
    )
    (net (code "55") (name "R18_GPIO_IO18") (class "Default")
      (node (ref "P11") (pin "12") (pinfunction "B6_12") (pintype "passive"))
    )
    (net (code "56") (name "R20_GPIO_IO17") (class "Default")
      (node (ref "P11") (pin "11") (pinfunction "A6_11") (pintype "passive"))
    )
    (net (code "57") (name "R21_GPIO_IO16") (class "Default")
      (node (ref "P11") (pin "36") (pinfunction "B18_36") (pintype "passive"))
    )
    (net (code "58") (name "T20_GPIO_IO20") (class "Default")
      (node (ref "P11") (pin "38") (pinfunction "B19_38") (pintype "passive"))
    )
    (net (code "59") (name "T21_GPIO_IO21") (class "Default")
      (node (ref "P11") (pin "40") (pinfunction "B20_40") (pintype "passive"))
    )
    (net (code "60") (name "U18_GPIO_IO22") (class "Default")
      (node (ref "P11") (pin "15") (pinfunction "A8_15") (pintype "passive"))
    )
    (net (code "61") (name "U20_GPIO_IO23") (class "Default")
      (node (ref "P11") (pin "16") (pinfunction "B8_16") (pintype "passive"))
    )
    (net (code "62") (name "U21_GPIO_IO24") (class "Default")
      (node (ref "P11") (pin "18") (pinfunction "B9_18") (pintype "passive"))
    )
    (net (code "63") (name "V4_CCM_CLKO4") (class "Default")
      (node (ref "Q23") (pin "2") (pinfunction "SOURCE_2") (pintype "passive"))
      (node (ref "R2895") (pin "1") (pinfunction "1_1") (pintype "passive"))
      (node (ref "R3060") (pin "2") (pinfunction "2_2") (pintype "passive"))
    )
    (net (code "64") (name "V20_GPIO_IO26") (class "Default")
      (node (ref "P11") (pin "37") (pinfunction "A19_37") (pintype "passive"))
    )
    (net (code "65") (name "V21_GPIO_IO25") (class "Default")
      (node (ref "P11") (pin "22") (pinfunction "B11_22") (pintype "passive"))
    )
    (net (code "66") (name "VDD_1V8") (class "Default")
      (node (ref "Q23") (pin "1") (pinfunction "GATE_1") (pintype "input"))
      (node (ref "R3060") (pin "1") (pinfunction "1_1") (pintype "passive"))
    )
    (net (code "67") (name "VDD_3V3") (class "Default")
      (node (ref "C966") (pin "1") (pinfunction "1_1") (pintype "passive"))
      (node (ref "C967") (pin "1") (pinfunction "1_1") (pintype "passive"))
      (node (ref "C982") (pin "1") (pinfunction "1_1") (pintype "passive"))
      (node (ref "C983") (pin "1") (pinfunction "1_1") (pintype "passive"))
      (node (ref "D618") (pin "2") (pinfunction "CATHODE_2") (pintype "passive"))
      (node (ref "D621") (pin "2") (pinfunction "CATHODE_2") (pintype "passive"))
      (node (ref "P12") (pin "1") (pinfunction "A1_1") (pintype "passive"))
      (node (ref "R2887") (pin "1") (pinfunction "1_1") (pintype "passive"))
      (node (ref "R2891") (pin "1") (pinfunction "1_1") (pintype "passive"))
      (node (ref "R3059") (pin "1") (pinfunction "1_1") (pintype "passive"))
      (node (ref "U732") (pin "A2") (pinfunction "IN_A2") (pintype "passive"))
    )
    (net (code "68") (name "VDD_5V") (class "Default")
      (node (ref "C976") (pin "1") (pinfunction "1_1") (pintype "passive"))
      (node (ref "C977") (pin "1") (pinfunction "1_1") (pintype "passive"))
      (node (ref "C984") (pin "1") (pinfunction "1_1") (pintype "passive"))
      (node (ref "C985") (pin "1") (pinfunction "1_1") (pintype "passive"))
      (node (ref "P12") (pin "2") (pinfunction "B1_2") (pintype "passive"))
      (node (ref "R3055") (pin "1") (pinfunction "1_1") (pintype "passive"))
      (node (ref "U733") (pin "1") (pinfunction "IN1_1") (pintype "passive"))
      (node (ref "U733") (pin "2") (pinfunction "IN2_2") (pintype "passive"))
      (node (ref "U733") (pin "3") (pinfunction "IN3_3") (pintype "passive"))
    )
    (net (code "69") (name "VEXP_3V3") (class "Default")
      (node (ref "C968") (pin "1") (pinfunction "1_1") (pintype "passive"))
      (node (ref "C969") (pin "1") (pinfunction "1_1") (pintype "passive"))
      (node (ref "C970") (pin "1") (pinfunction "1_1") (pintype "passive"))
      (node (ref "C971") (pin "1") (pinfunction "1_1") (pintype "passive"))
      (node (ref "P11") (pin "1") (pinfunction "A1_1") (pintype "passive"))
      (node (ref "P11") (pin "17") (pinfunction "A9_17") (pintype "passive"))
      (node (ref "R2893") (pin "1") (pinfunction "1_1") (pintype "passive"))
      (node (ref "U732") (pin "A1") (pinfunction "VOUT_A1") (pintype "passive"))
    )
    (net (code "70") (name "VEXP_5V") (class "Default")
      (node (ref "C972") (pin "1") (pinfunction "1_1") (pintype "passive"))
      (node (ref "C973") (pin "1") (pinfunction "1_1") (pintype "passive"))
      (node (ref "C978") (pin "1") (pinfunction "1_1") (pintype "passive"))
      (node (ref "C979") (pin "1") (pinfunction "1_1") (pintype "passive"))
      (node (ref "P11") (pin "2") (pinfunction "B1_2") (pintype "passive"))
      (node (ref "P11") (pin "4") (pinfunction "B2_4") (pintype "passive"))
      (node (ref "U733") (pin "10") (pinfunction "OUT1_10") (pintype "passive"))
      (node (ref "U733") (pin "8") (pinfunction "OUT3_8") (pintype "passive"))
      (node (ref "U733") (pin "9") (pinfunction "OUT2_9") (pintype "passive"))
    )
    (net (code "71") (name "VSD_3V3") (class "Default")
      (node (ref "C986") (pin "1") (pinfunction "1_1") (pintype "passive"))
      (node (ref "C987") (pin "1") (pinfunction "1_1") (pintype "passive"))
      (node (ref "D615") (pin "1") (pinfunction "1_1") (pintype "passive"))
      (node (ref "P13") (pin "4") (pinfunction "VDD_4") (pintype "power_in"))
    )
    (net (code "72") (name "W2_JTAG_TMS") (class "Default")
      (node (ref "P14") (pin "2") (pinfunction "2_2") (pintype "passive"))
    )
    (net (code "73") (name "W21_GPIO_IO27") (class "Default")
      (node (ref "P11") (pin "13") (pinfunction "A7_13") (pintype "passive"))
    )
    (net (code "74") (name "Y1_JTAG_TCK") (class "Default")
      (node (ref "P14") (pin "1") (pinfunction "1_1") (pintype "passive"))
    )
    (net (code "75") (name "Y17_SD2_nCD") (class "Default")
      (node (ref "R2896") (pin "1") (pinfunction "1_1") (pintype "passive"))
      (node (ref "R2897") (pin "2") (pinfunction "2_2") (pintype "passive"))
      (node (ref "R2899") (pin "1") (pinfunction "1_1") (pintype "passive"))
    )
    (net (code "76") (name "Y18_SD2_DATA0") (class "Default")
      (node (ref "R2902") (pin "1") (pinfunction "1_1") (pintype "passive"))
    )
    (net (code "77") (name "Y19_SD2_CMD") (class "Default")
      (node (ref "R2900") (pin "1") (pinfunction "1_1") (pintype "passive"))
    )
    (net (code "78") (name "Y20_SD2_DATA2") (class "Default")
      (node (ref "R2903") (pin "1") (pinfunction "1_1") (pintype "passive"))
    )
    (net (code "79") (name "unconnected-(D616-Pad3)") (class "Default")
      (node (ref "D616") (pin "3") (pinfunction "3_3") (pintype "passive+no_connect"))
    )
    (net (code "80") (name "unconnected-(D616-Pad4)") (class "Default")
      (node (ref "D616") (pin "4") (pinfunction "4_4") (pintype "passive+no_connect"))
    )
    (net (code "81") (name "unconnected-(D616-Pad6)") (class "Default")
      (node (ref "D616") (pin "6") (pinfunction "6_6") (pintype "passive+no_connect"))
    )
    (net (code "82") (name "unconnected-(D617-Pad3)") (class "Default")
      (node (ref "D617") (pin "3") (pinfunction "3_3") (pintype "passive+no_connect"))
    )
    (net (code "83") (name "unconnected-(D617-Pad6)") (class "Default")
      (node (ref "D617") (pin "6") (pinfunction "6_6") (pintype "passive+no_connect"))
    )
    (net (code "84") (name "unconnected-(P15-Pad4)") (class "Default")
      (node (ref "P15") (pin "4") (pinfunction "4_4") (pintype "passive+no_connect"))
    )
    (net (code "85") (name "unconnected-(P15-Pad6)") (class "Default")
      (node (ref "P15") (pin "6") (pinfunction "6_6") (pintype "passive+no_connect"))
    )
    (net (code "86") (name "unconnected-(P15-Pad7)") (class "Default")
      (node (ref "P15") (pin "7") (pinfunction "7_7") (pintype "passive+no_connect"))
    )
    (net (code "87") (name "unconnected-(P15-Pad8)") (class "Default")
      (node (ref "P15") (pin "8") (pinfunction "8_8") (pintype "passive+no_connect"))
    )
  )
)
